# CONNECTOR_EXP.net
KiCad netlist of a schematic drawn in Altium Designer
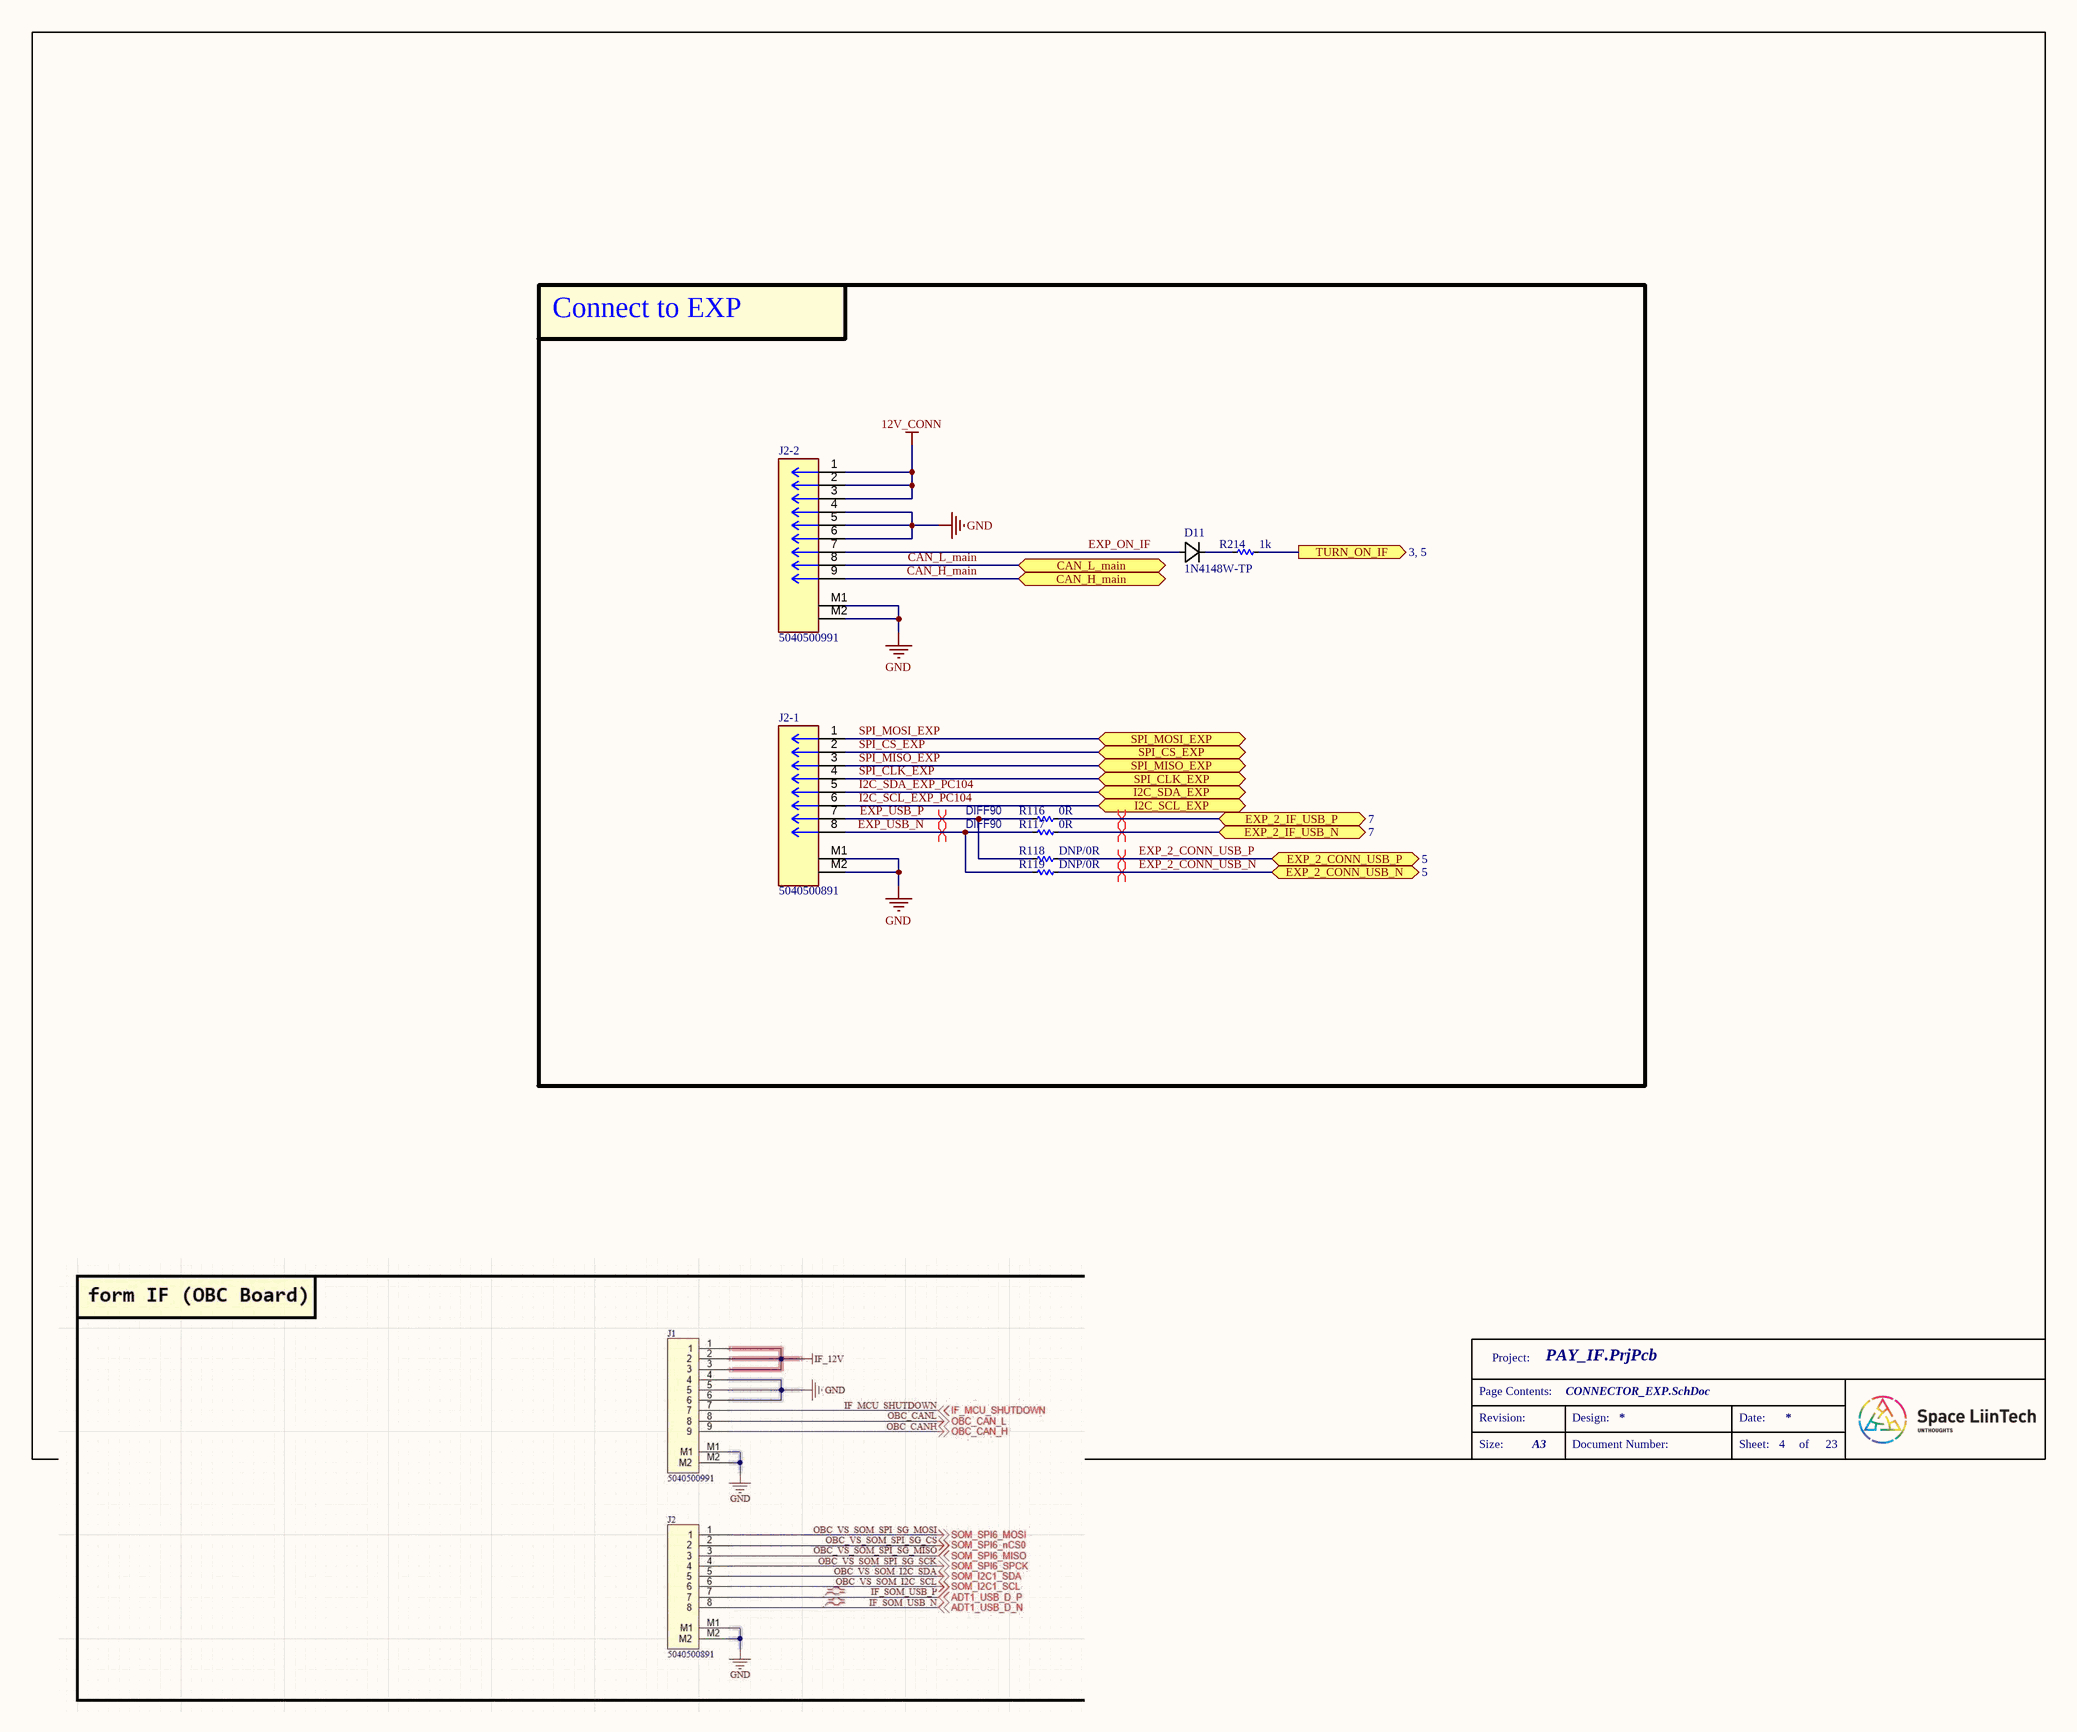
[diagram p0: CONNECTOR_EXP.SchDoc]

(export (version "E")
  (design (tool "Eeschema 10.0.6"))
  (components
    (comp (ref "D11")
      (value "1N4148W-TP")
      (footprint "SOD123_MCC")
      (description "Description")
      (fields (field (name "COPYRIGHT") "Copyright (C) 2026 Ultra Librarian. All rights reserved."))
      (libsource (lib "IFBschelib") (part "1N4148W-TP"))
    )
    (comp (ref "J2-1")
      (value "5040500891")
      (footprint "MOLEX_5040500891")
      (description "Connector Header Surface Mount, Right Angle 8 position 0.059\" (1.50mm)`")
      (libsource (lib "IFBschelib") (part "5040500891"))
    )
    (comp (ref "J2-2")
      (value "5040500991")
      (footprint "MOLEX_5040500991")
      (description "Connector Header Surface Mount, Right Angle 9 position 0.059\" (1.50mm)")
      (libsource (lib "IFBschelib") (part "5040500991"))
    )
    (comp (ref "R116")
      (value "0R")
      (footprint "RES_C_0603X30")
      (description "RES")
      (libsource (lib "IFBschelib") (part "_RES_B_2"))
    )
    (comp (ref "R117")
      (value "0R")
      (footprint "RES_C_0603X30")
      (description "RES")
      (libsource (lib "IFBschelib") (part "_RES_B_2"))
    )
    (comp (ref "R118")
      (value "DNP/0R")
      (footprint "RES_C_0603X30")
      (description "RES")
      (libsource (lib "IFBschelib") (part "_RES_B_2"))
    )
    (comp (ref "R119")
      (value "DNP/0R")
      (footprint "RES_C_0603X30")
      (description "RES")
      (libsource (lib "IFBschelib") (part "_RES_B_2"))
    )
    (comp (ref "R214")
      (value "1k")
      (footprint "RES_C_1005x30_L")
      (description "RES")
      (libsource (lib "IFBschelib") (part "_RES_B_2"))
    )
  )
  (nets
    (net (code "1") (name "/CAN_H_main") (class "Default")
      (node (ref "J2-2") (pin "9") (pinfunction "9_9") (pintype "passive"))
    )
    (net (code "2") (name "/CAN_L_main") (class "Default")
      (node (ref "J2-2") (pin "8") (pinfunction "8_8") (pintype "passive"))
    )
    (net (code "3") (name "/EXP_2_CONN_USB_N") (class "Default")
      (node (ref "R119") (pin "2") (pinfunction "2_2") (pintype "passive"))
    )
    (net (code "4") (name "/EXP_2_CONN_USB_P") (class "Default")
      (node (ref "R118") (pin "2") (pinfunction "2_2") (pintype "passive"))
    )
    (net (code "5") (name "/EXP_2_IF_USB_N") (class "Default")
      (node (ref "R117") (pin "2") (pinfunction "2_2") (pintype "passive"))
    )
    (net (code "6") (name "/EXP_2_IF_USB_P") (class "Default")
      (node (ref "R116") (pin "2") (pinfunction "2_2") (pintype "passive"))
    )
    (net (code "7") (name "/EXP_ON_IF") (class "Default")
      (node (ref "D11") (pin "2") (pinfunction "2_2") (pintype "passive"))
      (node (ref "J2-2") (pin "7") (pinfunction "7_7") (pintype "passive"))
    )
    (net (code "8") (name "/EXP_USB_N") (class "Default")
      (node (ref "J2-1") (pin "8") (pinfunction "8_8") (pintype "passive"))
      (node (ref "R117") (pin "1") (pinfunction "1_1") (pintype "passive"))
      (node (ref "R119") (pin "1") (pinfunction "1_1") (pintype "passive"))
    )
    (net (code "9") (name "/EXP_USB_P") (class "Default")
      (node (ref "J2-1") (pin "7") (pinfunction "7_7") (pintype "passive"))
      (node (ref "R116") (pin "1") (pinfunction "1_1") (pintype "passive"))
      (node (ref "R118") (pin "1") (pinfunction "1_1") (pintype "passive"))
    )
    (net (code "10") (name "/I2C_SCL_EXP_PC104") (class "Default")
      (node (ref "J2-1") (pin "6") (pinfunction "6_6") (pintype "passive"))
    )
    (net (code "11") (name "/I2C_SDA_EXP_PC104") (class "Default")
      (node (ref "J2-1") (pin "5") (pinfunction "5_5") (pintype "passive"))
    )
    (net (code "12") (name "/SPI_CLK_EXP") (class "Default")
      (node (ref "J2-1") (pin "4") (pinfunction "4_4") (pintype "passive"))
    )
    (net (code "13") (name "/SPI_CS_EXP") (class "Default")
      (node (ref "J2-1") (pin "2") (pinfunction "2_2") (pintype "passive"))
    )
    (net (code "14") (name "/SPI_MISO_EXP") (class "Default")
      (node (ref "J2-1") (pin "3") (pinfunction "3_3") (pintype "passive"))
    )
    (net (code "15") (name "/SPI_MOSI_EXP") (class "Default")
      (node (ref "J2-1") (pin "1") (pinfunction "1_1") (pintype "passive"))
    )
    (net (code "16") (name "/TURN_ON_IF") (class "Default")
      (node (ref "R214") (pin "2") (pinfunction "2_2") (pintype "passive"))
    )
    (net (code "17") (name "12V_CONN") (class "Default")
      (node (ref "J2-2") (pin "1") (pinfunction "1_1") (pintype "passive"))
      (node (ref "J2-2") (pin "2") (pinfunction "2_2") (pintype "passive"))
      (node (ref "J2-2") (pin "3") (pinfunction "3_3") (pintype "passive"))
    )
    (net (code "18") (name "GND") (class "Default")
      (node (ref "J2-1") (pin "M1") (pinfunction "M1_M1") (pintype "passive"))
      (node (ref "J2-1") (pin "M2") (pinfunction "M2_M2") (pintype "passive"))
      (node (ref "J2-2") (pin "4") (pinfunction "4_4") (pintype "passive"))
      (node (ref "J2-2") (pin "5") (pinfunction "5_5") (pintype "passive"))
      (node (ref "J2-2") (pin "6") (pinfunction "6_6") (pintype "passive"))
      (node (ref "J2-2") (pin "M1") (pinfunction "M1_M1") (pintype "passive"))
      (node (ref "J2-2") (pin "M2") (pinfunction "M2_M2") (pintype "passive"))
    )
    (net (code "19") (name "Net-(D11-Pad1)") (class "Default")
      (node (ref "D11") (pin "1") (pinfunction "1_1") (pintype "passive"))
      (node (ref "R214") (pin "1") (pinfunction "1_1") (pintype "passive"))
    )
  )
)
